# miner_protector.net
KiCad netlist of a schematic drawn in Altium Designer
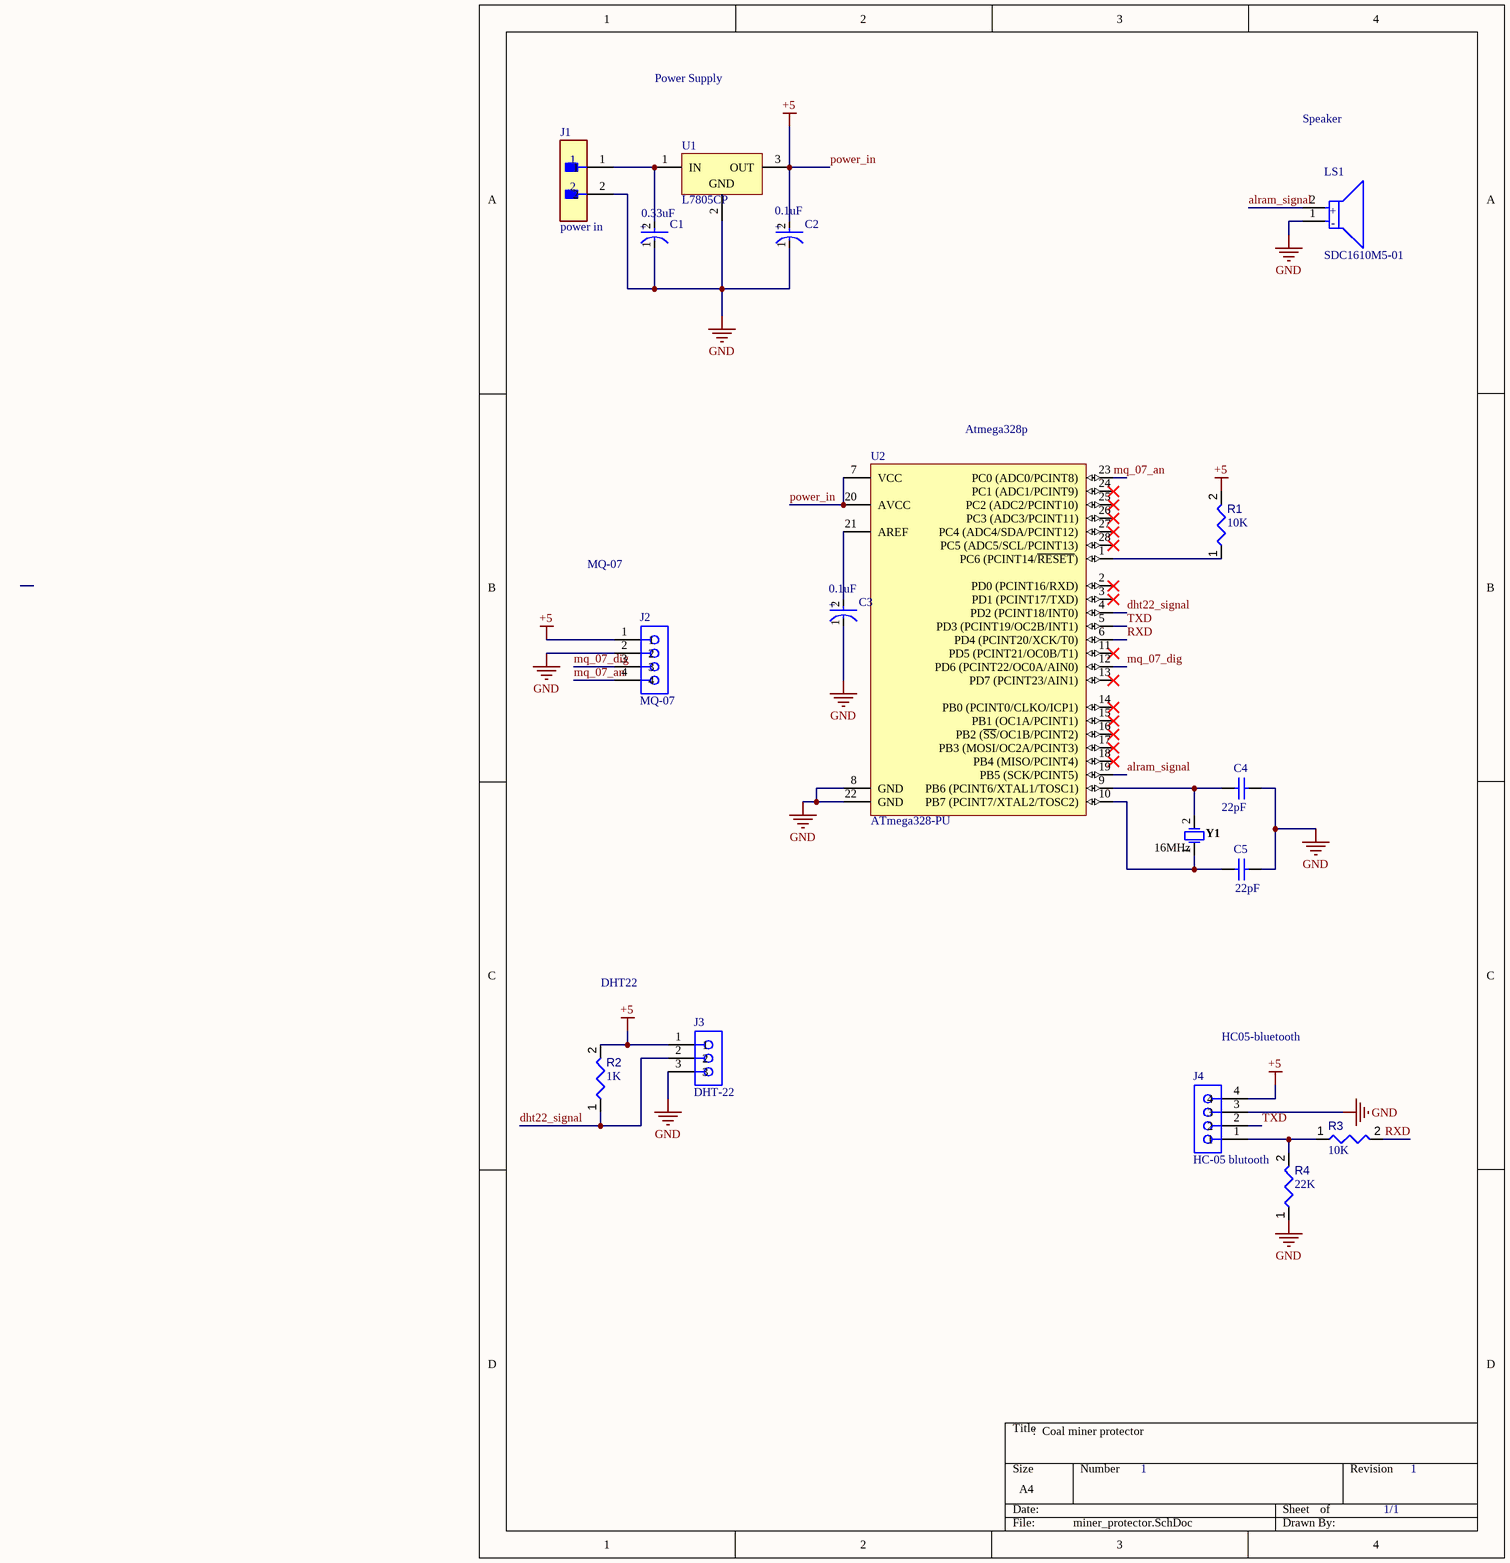
[diagram p0: miner_protector.SchDoc]

(export (version "E")
  (design (tool "Eeschema 10.0.6"))
  (components
    (comp (ref "C1")
      (value "EEUFM1H121LB")
      (footprint "FP-RAD-TH-D_8_0_5-L_15_1-MFG")
      (description "Aluminum Electrolytic Capacitors (Radial Lead Type) 120uF ±20% 50V")
      (fields (field (name "TOLERANCE") "20%") (field (name "CAPACITANCE") "0.33uF"))
      (libsource (lib "Altium Content Vault") (part "a00bbbee19879c290e62620ae7e47b1"))
    )
    (comp (ref "C2")
      (value "EEUFM1H121LB")
      (footprint "FP-RAD-TH-D_8_0_5-L_15_1-MFG")
      (description "Aluminum Electrolytic Capacitors (Radial Lead Type) 120uF ±20% 50V")
      (fields (field (name "TOLERANCE") "20%") (field (name "CAPACITANCE") "0.1uF"))
      (libsource (lib "Altium Content Vault") (part "a00bbbee19879c290e62620ae7e47b1"))
    )
    (comp (ref "C3")
      (value "EEUFM1H121LB")
      (footprint "FP-RAD-TH-D_8_0_5-L_15_1-MFG")
      (description "Aluminum Electrolytic Capacitors (Radial Lead Type) 120uF ±20% 50V")
      (fields (field (name "TOLERANCE") "20%") (field (name "CAPACITANCE") "0.1uF"))
      (libsource (lib "Altium Content Vault") (part "a00bbbee19879c290e62620ae7e47b1"))
    )
    (comp (ref "C4")
      (value "C330C105M5U5TA")
      (footprint "KEMT-C330C105M5U5TA")
      (description "Ceramic Capacitor, 1 uF, +/- 20%, 50 V, -10 to 85 degC, 2-Pin THD, RoHS, Bulk")
      (fields
        (field (name "TOLERANCE") "±20%")
        (field (name "CAPACITANCE") "22pF")
        (field (name "MANUFACTURER") "Kemet")
      )
      (libsource (lib "Altium Content Vault") (part "CAP-NP-2"))
    )
    (comp (ref "C5")
      (value "C330C105M5U5TA")
      (footprint "KEMT-C330C105M5U5TA")
      (description "Ceramic Capacitor, 1 uF, +/- 20%, 50 V, -10 to 85 degC, 2-Pin THD, RoHS, Bulk")
      (fields
        (field (name "TOLERANCE") "±20%")
        (field (name "CAPACITANCE") "22pF")
        (field (name "MANUFACTURER") "Kemet")
      )
      (libsource (lib "Altium Content Vault") (part "CAP-NP-2"))
    )
    (comp (ref "J1")
      (value "power in")
      (footprint "FP-TSW-102-07-L-S-MFG")
      (description "CONN HEADER VERT 2POS 2.54MM")
      (libsource (lib "Altium Content Vault") (part "3bc925449376181038e59eaffc5286c"))
    )
    (comp (ref "J2")
      (value "MQ-07")
      (footprint "SMTC-SLW-104-01-X-S")
      (fields (field (name "MANUFACTURER") "Samtec") (field (name "PARTNUMBER") "SLW-104-01-T-S"))
      (libsource (lib "Altium Content Vault") (part "SMTC-SLW-104-01-X-S"))
    )
    (comp (ref "J3")
      (value "DHT-22")
      (footprint "SMTC-BCS-103-X-S-TE")
      (description "Tiger Claw(TM) Pass-Through Socket, Vertical, -55 to 125 degC, 2.54 mm Pitch, 3-Pin, Female, RoHS")
      (fields (field (name "PARTNUMBER") "BCS-103-L-S-TE") (field (name "MANUFACTURER") "Samtec"))
      (libsource (lib "Altium Content Vault") (part "SMTC-BCS-103-X-S-TE"))
    )
    (comp (ref "J4")
      (value "HC-05 blutooth")
      (footprint "SMTC-SLW-104-01-X-S")
      (fields (field (name "MANUFACTURER") "Samtec") (field (name "PARTNUMBER") "SLW-104-01-T-S"))
      (libsource (lib "Altium Content Vault") (part "SMTC-SLW-104-01-X-S"))
    )
    (comp (ref "LS1")
      (value "SDC1610M5-01")
      (footprint "FP-SDC1610M5-01-MFG")
      (description "AUDIO MAGNETIC INDICATOR 4-8V TH")
      (libsource (lib "Altium Content Vault") (part "f7ec632b6fea80cbef86dc3340f200c"))
    )
    (comp (ref "R1")
      (value "10K")
      (footprint "RESA60-630X240")
      (description "Axial Resistor, 475 Ohm, +/- 1%, 0.25 W, -55 to 155 degC, 2-Pin THD, RoHS, Bulk")
      (fields (field (name "MANUFACTURER") "Yageo") (field (name "TOLERANCE") "1%"))
      (libsource (lib "uom_pesala") (part "RES-2"))
    )
    (comp (ref "R2")
      (value "1K")
      (footprint "RESA60-630X240")
      (description "Axial Resistor, 475 Ohm, +/- 1%, 0.25 W, -55 to 155 degC, 2-Pin THD, RoHS, Bulk")
      (fields (field (name "MANUFACTURER") "Yageo") (field (name "TOLERANCE") "1%"))
      (libsource (lib "uom_pesala") (part "RES-2"))
    )
    (comp (ref "R3")
      (value "10K")
      (footprint "RESA60-630X240")
      (description "Axial Resistor, 475 Ohm, +/- 1%, 0.25 W, -55 to 155 degC, 2-Pin THD, RoHS, Bulk")
      (fields (field (name "MANUFACTURER") "Yageo") (field (name "TOLERANCE") "1%"))
      (libsource (lib "uom_pesala") (part "RES-2"))
    )
    (comp (ref "R4")
      (value "22K")
      (footprint "RESA60-630X240")
      (description "Axial Resistor, 475 Ohm, +/- 1%, 0.25 W, -55 to 155 degC, 2-Pin THD, RoHS, Bulk")
      (fields (field (name "MANUFACTURER") "Yageo") (field (name "TOLERANCE") "1%"))
      (libsource (lib "uom_pesala") (part "RES-2"))
    )
    (comp (ref "U1")
      (value "L7805CP")
      (footprint "TO220FP")
      (description "Positive Voltage Regulator, 5V, 3-Pin TO-220FP")
      (libsource (lib "Altium Content Vault") (part "PM-REG-L4940-SIL3"))
    )
    (comp (ref "U2")
      (value "ATmega328-PU")
      (footprint "28P3")
      (libsource (lib "Altium Content Vault") (part "MC-8B-ATM48-IL28"))
    )
    (comp (ref "Y1")
      (value "16MHz")
      (footprint "FOX-FOXSLF160-20")
      (description "Resistance Weld Thru-Hole Crystal, 16 MHz, -20 to 70 degC, 2-Pin THD, RoHS, Bulk")
      (fields (field (name "TOLERANCE") "1%"))
      (libsource (lib "Altium Content Vault") (part "XTAL-1-2-2"))
    )
  )
  (nets
    (net (code "1") (name "+5") (class "Default")
      (node (ref "C2") (pin "2") (pinfunction "A_2") (pintype "passive"))
      (node (ref "J2") (pin "1") (pinfunction "1_1") (pintype "passive"))
      (node (ref "J3") (pin "1") (pinfunction "1_1") (pintype "passive"))
      (node (ref "J4") (pin "4") (pinfunction "4_4") (pintype "passive"))
      (node (ref "R1") (pin "2") (pinfunction "2_2") (pintype "passive"))
      (node (ref "R2") (pin "2") (pinfunction "2_2") (pintype "passive"))
      (node (ref "U1") (pin "3") (pinfunction "OUT_3") (pintype "power_in"))
      (node (ref "U2") (pin "20") (pinfunction "AVCC_20") (pintype "power_in"))
      (node (ref "U2") (pin "7") (pinfunction "VCC_7") (pintype "power_in"))
    )
    (net (code "2") (name "/RXD") (class "Default")
      (node (ref "R3") (pin "2") (pinfunction "2_2") (pintype "passive"))
      (node (ref "U2") (pin "6") (pinfunction "PD4_(PCINT20/XCK/T0)_6") (pintype "bidirectional"))
    )
    (net (code "3") (name "/TXD") (class "Default")
      (node (ref "J4") (pin "2") (pinfunction "2_2") (pintype "passive"))
      (node (ref "U2") (pin "5") (pinfunction "PD3_(PCINT19/OC2B/INT1)_5") (pintype "bidirectional"))
    )
    (net (code "4") (name "/alram_signal") (class "Default")
      (node (ref "LS1") (pin "2") (pinfunction "A_2") (pintype "passive"))
      (node (ref "U2") (pin "19") (pinfunction "PB5_(SCK/PCINT5)_19") (pintype "bidirectional"))
    )
    (net (code "5") (name "/dht22_signal") (class "Default")
      (node (ref "J3") (pin "2") (pinfunction "2_2") (pintype "passive"))
      (node (ref "R2") (pin "1") (pinfunction "1_1") (pintype "passive"))
      (node (ref "U2") (pin "4") (pinfunction "PD2_(PCINT18/INT0)_4") (pintype "bidirectional"))
    )
    (net (code "6") (name "/mq_07_an") (class "Default")
      (node (ref "J2") (pin "4") (pinfunction "4_4") (pintype "passive"))
      (node (ref "U2") (pin "23") (pinfunction "PC0_(ADC0/PCINT8)_23") (pintype "bidirectional"))
    )
    (net (code "7") (name "/mq_07_dig") (class "Default")
      (node (ref "J2") (pin "3") (pinfunction "3_3") (pintype "passive"))
      (node (ref "U2") (pin "12") (pinfunction "PD6_(PCINT22/OC0A/AIN0)_12") (pintype "bidirectional"))
    )
    (net (code "8") (name "GND") (class "Default")
      (node (ref "C1") (pin "1") (pinfunction "C_1") (pintype "passive"))
      (node (ref "C2") (pin "1") (pinfunction "C_1") (pintype "passive"))
      (node (ref "C3") (pin "1") (pinfunction "C_1") (pintype "passive"))
      (node (ref "C4") (pin "2") (pinfunction "2_2") (pintype "passive"))
      (node (ref "C5") (pin "2") (pinfunction "2_2") (pintype "passive"))
      (node (ref "J1") (pin "2") (pinfunction "2_2") (pintype "passive"))
      (node (ref "J2") (pin "2") (pinfunction "2_2") (pintype "passive"))
      (node (ref "J3") (pin "3") (pinfunction "3_3") (pintype "passive"))
      (node (ref "J4") (pin "3") (pinfunction "3_3") (pintype "passive"))
      (node (ref "LS1") (pin "1") (pinfunction "C_1") (pintype "passive"))
      (node (ref "R4") (pin "1") (pinfunction "1_1") (pintype "passive"))
      (node (ref "U1") (pin "2") (pinfunction "GND_2") (pintype "power_in"))
      (node (ref "U2") (pin "22") (pinfunction "GND_22") (pintype "power_in"))
      (node (ref "U2") (pin "8") (pinfunction "GND_8") (pintype "power_in"))
    )
    (net (code "9") (name "Net-(C1-A)") (class "Default")
      (node (ref "C1") (pin "2") (pinfunction "A_2") (pintype "passive"))
      (node (ref "J1") (pin "1") (pinfunction "1_1") (pintype "passive"))
      (node (ref "U1") (pin "1") (pinfunction "IN_1") (pintype "power_in"))
    )
    (net (code "10") (name "Net-(C3-A)") (class "Default")
      (node (ref "C3") (pin "2") (pinfunction "A_2") (pintype "passive"))
      (node (ref "U2") (pin "21") (pinfunction "AREF_21") (pintype "power_in"))
    )
    (net (code "11") (name "Net-(J4-Pad1)") (class "Default")
      (node (ref "J4") (pin "1") (pinfunction "1_1") (pintype "passive"))
      (node (ref "R3") (pin "1") (pinfunction "1_1") (pintype "passive"))
      (node (ref "R4") (pin "2") (pinfunction "2_2") (pintype "passive"))
    )
    (net (code "12") (name "Net-(U2-PB6_(PCINT6{slash}XTAL1{slash}TOSC1))") (class "Default")
      (node (ref "C4") (pin "1") (pinfunction "1_1") (pintype "passive"))
      (node (ref "U2") (pin "9") (pinfunction "PB6_(PCINT6/XTAL1/TOSC1)_9") (pintype "bidirectional"))
      (node (ref "Y1") (pin "2") (pinfunction "2_2") (pintype "passive"))
    )
    (net (code "13") (name "Net-(U2-PB7_(PCINT7{slash}XTAL2{slash}TOSC2))") (class "Default")
      (node (ref "C5") (pin "1") (pinfunction "1_1") (pintype "passive"))
      (node (ref "U2") (pin "10") (pinfunction "PB7_(PCINT7/XTAL2/TOSC2)_10") (pintype "bidirectional"))
      (node (ref "Y1") (pin "1") (pinfunction "1_1") (pintype "passive"))
    )
    (net (code "14") (name "Net-(U2-PC6_(PCINT14{slash}~{RESET}))") (class "Default")
      (node (ref "R1") (pin "1") (pinfunction "1_1") (pintype "passive"))
      (node (ref "U2") (pin "1") (pinfunction "PC6_(PCINT14/~{RESET})_1") (pintype "bidirectional"))
    )
    (net (code "15") (name "unconnected-(U2-PB0_(PCINT0{slash}CLKO{slash}ICP1)-Pad14)") (class "Default")
      (node (ref "U2") (pin "14") (pinfunction "PB0_(PCINT0/CLKO/ICP1)_14") (pintype "bidirectional+no_connect"))
    )
    (net (code "16") (name "unconnected-(U2-PB1_(OC1A{slash}PCINT1)-Pad15)") (class "Default")
      (node (ref "U2") (pin "15") (pinfunction "PB1_(OC1A/PCINT1)_15") (pintype "bidirectional+no_connect"))
    )
    (net (code "17") (name "unconnected-(U2-PB2_(~{SS}{slash}OC1B{slash}PCINT2)-Pad16)") (class "Default")
      (node (ref "U2") (pin "16") (pinfunction "PB2_(~{SS}/OC1B/PCINT2)_16") (pintype "bidirectional+no_connect"))
    )
    (net (code "18") (name "unconnected-(U2-PB3_(MOSI{slash}OC2A{slash}PCINT3)-Pad17)") (class "Default")
      (node (ref "U2") (pin "17") (pinfunction "PB3_(MOSI/OC2A/PCINT3)_17") (pintype "bidirectional+no_connect"))
    )
    (net (code "19") (name "unconnected-(U2-PB4_(MISO{slash}PCINT4)-Pad18)") (class "Default")
      (node (ref "U2") (pin "18") (pinfunction "PB4_(MISO/PCINT4)_18") (pintype "bidirectional+no_connect"))
    )
    (net (code "20") (name "unconnected-(U2-PC1_(ADC1{slash}PCINT9)-Pad24)") (class "Default")
      (node (ref "U2") (pin "24") (pinfunction "PC1_(ADC1/PCINT9)_24") (pintype "bidirectional+no_connect"))
    )
    (net (code "21") (name "unconnected-(U2-PC2_(ADC2{slash}PCINT10)-Pad25)") (class "Default")
      (node (ref "U2") (pin "25") (pinfunction "PC2_(ADC2/PCINT10)_25") (pintype "bidirectional+no_connect"))
    )
    (net (code "22") (name "unconnected-(U2-PC3_(ADC3{slash}PCINT11)-Pad26)") (class "Default")
      (node (ref "U2") (pin "26") (pinfunction "PC3_(ADC3/PCINT11)_26") (pintype "bidirectional+no_connect"))
    )
    (net (code "23") (name "unconnected-(U2-PC4_(ADC4{slash}SDA{slash}PCINT12)-Pad27)") (class "Default")
      (node (ref "U2") (pin "27") (pinfunction "PC4_(ADC4/SDA/PCINT12)_27") (pintype "bidirectional+no_connect"))
    )
    (net (code "24") (name "unconnected-(U2-PC5_(ADC5{slash}SCL{slash}PCINT13)-Pad28)") (class "Default")
      (node (ref "U2") (pin "28") (pinfunction "PC5_(ADC5/SCL/PCINT13)_28") (pintype "bidirectional+no_connect"))
    )
    (net (code "25") (name "unconnected-(U2-PD0_(PCINT16{slash}RXD)-Pad2)") (class "Default")
      (node (ref "U2") (pin "2") (pinfunction "PD0_(PCINT16/RXD)_2") (pintype "bidirectional+no_connect"))
    )
    (net (code "26") (name "unconnected-(U2-PD1_(PCINT17{slash}TXD)-Pad3)") (class "Default")
      (node (ref "U2") (pin "3") (pinfunction "PD1_(PCINT17/TXD)_3") (pintype "bidirectional+no_connect"))
    )
    (net (code "27") (name "unconnected-(U2-PD5_(PCINT21{slash}OC0B{slash}T1)-Pad11)") (class "Default")
      (node (ref "U2") (pin "11") (pinfunction "PD5_(PCINT21/OC0B/T1)_11") (pintype "bidirectional+no_connect"))
    )
    (net (code "28") (name "unconnected-(U2-PD7_(PCINT23{slash}AIN1)-Pad13)") (class "Default")
      (node (ref "U2") (pin "13") (pinfunction "PD7_(PCINT23/AIN1)_13") (pintype "bidirectional+no_connect"))
    )
  )
)
